# SOCUSBHSPHY.net
KiCad netlist of a schematic drawn in Altium Designer
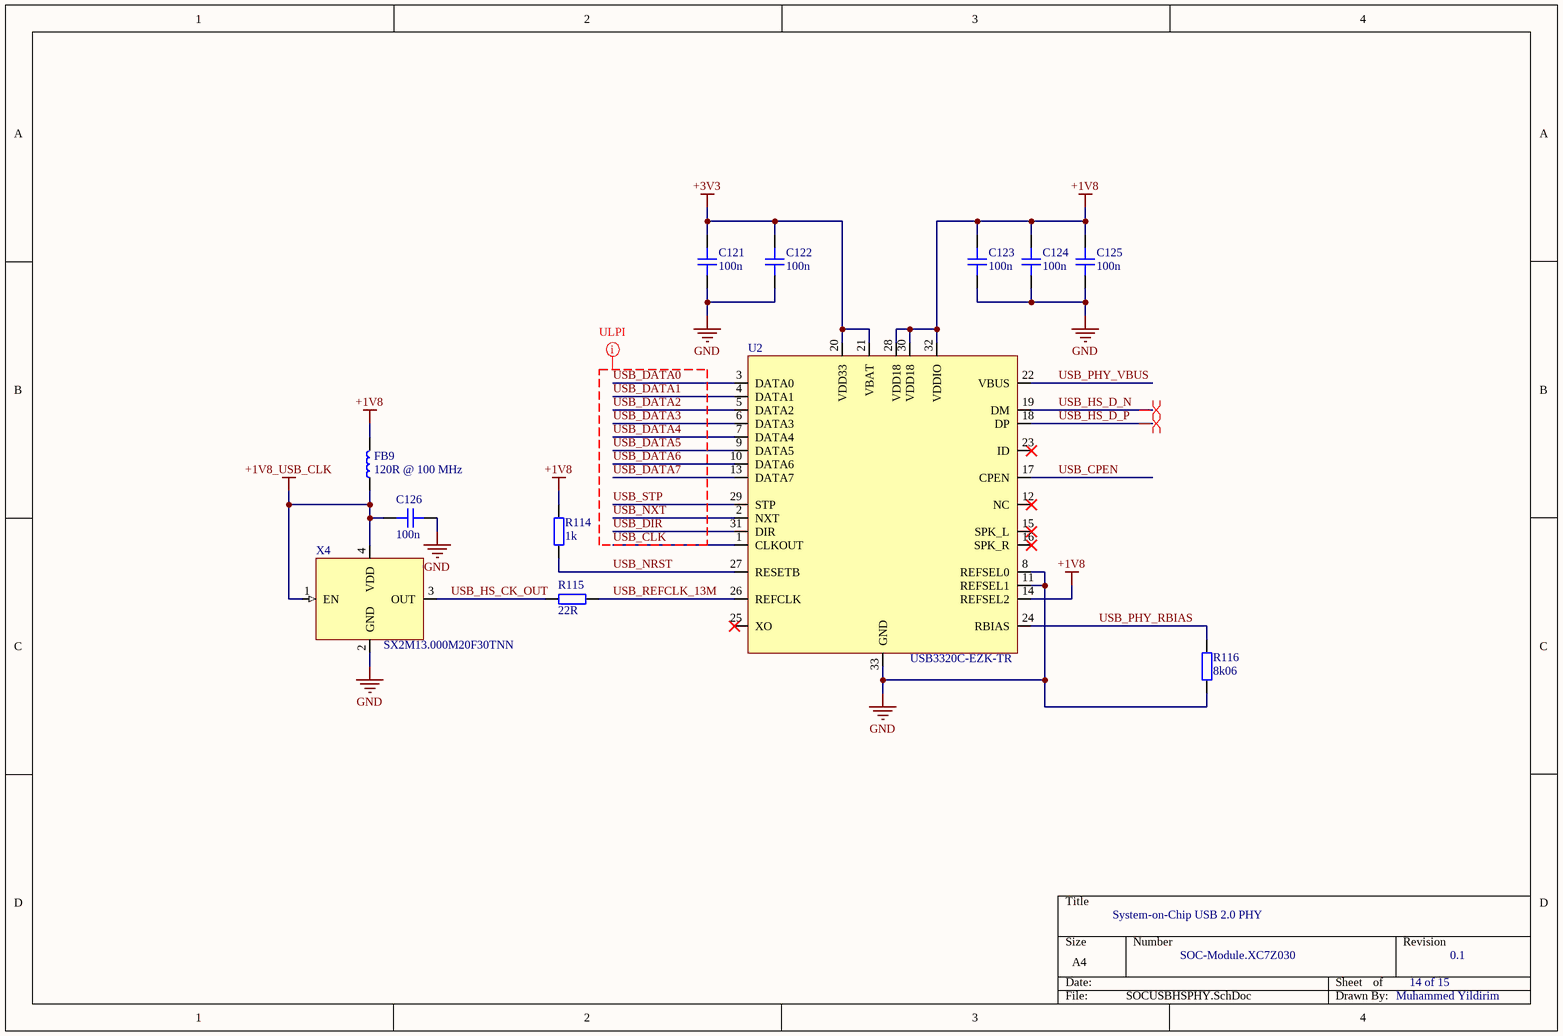
[diagram p0: SOCUSBHSPHY.SchDoc]

(export (version "E")
  (design (tool "Eeschema 10.0.6"))
  (components
    (comp (ref "C121")
      (value "100n")
      (footprint "CAP_0201")
      (description "Capacitor SMD 0201")
      (libsource (lib "Schematic-Lib-PhilsLab") (part "CAP_0201"))
    )
    (comp (ref "C122")
      (value "100n")
      (footprint "CAP_0201")
      (description "Capacitor SMD 0201")
      (libsource (lib "Schematic-Lib-PhilsLab") (part "CAP_0201"))
    )
    (comp (ref "C123")
      (value "100n")
      (footprint "CAP_0201")
      (description "Capacitor SMD 0201")
      (libsource (lib "Schematic-Lib-PhilsLab") (part "CAP_0201"))
    )
    (comp (ref "C124")
      (value "100n")
      (footprint "CAP_0201")
      (description "Capacitor SMD 0201")
      (libsource (lib "Schematic-Lib-PhilsLab") (part "CAP_0201"))
    )
    (comp (ref "C125")
      (value "100n")
      (footprint "CAP_0201")
      (description "Capacitor SMD 0201")
      (libsource (lib "Schematic-Lib-PhilsLab") (part "CAP_0201"))
    )
    (comp (ref "C126")
      (value "100n")
      (footprint "CAP_0201")
      (description "Capacitor SMD 0201")
      (libsource (lib "Schematic-Lib-PhilsLab") (part "CAP_0201"))
    )
    (comp (ref "FB9")
      (value "120R @ 100 MHz")
      (footprint "Footprint-Lib-PhilsLab:IND_0201")
      (description "Inductor SMD 0201")
      (fields
        (field (name "MANUFACTURER_PART_NUMBER") "LQP03HQ56NH02D")
        (field (name "MOUSER PART NUMBER") "81-LQP03HQ56NH02D")
      )
      (libsource (lib "Schematic-Lib-PhilsLab") (part "IND_0201"))
    )
    (comp (ref "R114")
      (value "1k")
      (footprint "RES_0201")
      (description "Resistor SMD 0201")
      (libsource (lib "Schematic-Lib-PhilsLab") (part "RES_0201"))
    )
    (comp (ref "R115")
      (value "22R")
      (footprint "RES_0201")
      (description "Resistor SMD 0201")
      (libsource (lib "Schematic-Lib-PhilsLab") (part "RES_0201"))
    )
    (comp (ref "R116")
      (value "8k06")
      (footprint "RES_0201")
      (description "Resistor SMD 0201")
      (libsource (lib "Schematic-Lib-PhilsLab") (part "RES_0201"))
    )
    (comp (ref "U2")
      (value "USB3320C-EZK-TR")
      (footprint "QFN-32-5x5x0.85mm")
      (description "Hi-Speed USB 2.0 ULPI Transceiver")
      (fields (field (name "MANUFACTURER") "Microchip"))
      (libsource (lib "Schematic-Lib-PhilsLab") (part "USB3320C-EZK-TR"))
    )
    (comp (ref "X4")
      (value "SX2M13.000M20F30TNN")
      (footprint "XTAL_2520")
      (fields
        (field (name "MANUFACTURER") "ECS")
        (field (name "MANUFACTURER PART NUMBER") "ECS-2520MV-130-BN-TR")
      )
      (libsource (lib "Schematic-Lib-PhilsLab") (part "ECS-2520MV-130-BN-TR"))
    )
  )
  (nets
    (net (code "1") (name "+1V8") (class "Default")
      (node (ref "C123") (pin "2") (pinfunction "2_2") (pintype "passive"))
      (node (ref "C124") (pin "2") (pinfunction "2_2") (pintype "passive"))
      (node (ref "C125") (pin "2") (pinfunction "2_2") (pintype "passive"))
      (node (ref "FB9") (pin "2") (pinfunction "2_2") (pintype "passive"))
      (node (ref "R114") (pin "1") (pinfunction "1_1") (pintype "passive"))
      (node (ref "U2") (pin "14") (pinfunction "REFSEL2_14") (pintype "passive"))
      (node (ref "U2") (pin "28") (pinfunction "VDD18_28") (pintype "passive"))
      (node (ref "U2") (pin "30") (pinfunction "VDD18_30") (pintype "passive"))
      (node (ref "U2") (pin "32") (pinfunction "VDDIO_32") (pintype "passive"))
    )
    (net (code "2") (name "+1V8_USB_CLK") (class "Default")
      (node (ref "C126") (pin "2") (pinfunction "2_2") (pintype "passive"))
      (node (ref "FB9") (pin "1") (pinfunction "1_1") (pintype "passive"))
      (node (ref "X4") (pin "1") (pinfunction "EN_1") (pintype "input"))
      (node (ref "X4") (pin "4") (pinfunction "VDD_4") (pintype "power_in"))
    )
    (net (code "3") (name "+3V3") (class "Default")
      (node (ref "C121") (pin "2") (pinfunction "2_2") (pintype "passive"))
      (node (ref "C122") (pin "2") (pinfunction "2_2") (pintype "passive"))
      (node (ref "U2") (pin "20") (pinfunction "VDD33_20") (pintype "passive"))
      (node (ref "U2") (pin "21") (pinfunction "VBAT_21") (pintype "passive"))
    )
    (net (code "4") (name "/USB_CLK") (class "Default")
      (node (ref "U2") (pin "1") (pinfunction "CLKOUT_1") (pintype "passive"))
    )
    (net (code "5") (name "/USB_CPEN") (class "Default")
      (node (ref "U2") (pin "17") (pinfunction "CPEN_17") (pintype "passive"))
    )
    (net (code "6") (name "/USB_DATA0") (class "Default")
      (node (ref "U2") (pin "3") (pinfunction "DATA0_3") (pintype "passive"))
    )
    (net (code "7") (name "/USB_DATA1") (class "Default")
      (node (ref "U2") (pin "4") (pinfunction "DATA1_4") (pintype "passive"))
    )
    (net (code "8") (name "/USB_DATA2") (class "Default")
      (node (ref "U2") (pin "5") (pinfunction "DATA2_5") (pintype "passive"))
    )
    (net (code "9") (name "/USB_DATA3") (class "Default")
      (node (ref "U2") (pin "6") (pinfunction "DATA3_6") (pintype "passive"))
    )
    (net (code "10") (name "/USB_DATA4") (class "Default")
      (node (ref "U2") (pin "7") (pinfunction "DATA4_7") (pintype "passive"))
    )
    (net (code "11") (name "/USB_DATA5") (class "Default")
      (node (ref "U2") (pin "9") (pinfunction "DATA5_9") (pintype "passive"))
    )
    (net (code "12") (name "/USB_DATA6") (class "Default")
      (node (ref "U2") (pin "10") (pinfunction "DATA6_10") (pintype "passive"))
    )
    (net (code "13") (name "/USB_DATA7") (class "Default")
      (node (ref "U2") (pin "13") (pinfunction "DATA7_13") (pintype "passive"))
    )
    (net (code "14") (name "/USB_DIR") (class "Default")
      (node (ref "U2") (pin "31") (pinfunction "DIR_31") (pintype "passive"))
    )
    (net (code "15") (name "/USB_HS_CK_OUT") (class "Default")
      (node (ref "R115") (pin "1") (pinfunction "1_1") (pintype "passive"))
      (node (ref "X4") (pin "3") (pinfunction "OUT_3") (pintype "passive"))
    )
    (net (code "16") (name "/USB_HS_D_N") (class "Default")
      (node (ref "U2") (pin "19") (pinfunction "DM_19") (pintype "passive"))
    )
    (net (code "17") (name "/USB_HS_D_P") (class "Default")
      (node (ref "U2") (pin "18") (pinfunction "DP_18") (pintype "passive"))
    )
    (net (code "18") (name "/USB_NRST") (class "Default")
      (node (ref "R114") (pin "2") (pinfunction "2_2") (pintype "passive"))
      (node (ref "U2") (pin "27") (pinfunction "RESETB_27") (pintype "passive"))
    )
    (net (code "19") (name "/USB_NXT") (class "Default")
      (node (ref "U2") (pin "2") (pinfunction "NXT_2") (pintype "passive"))
    )
    (net (code "20") (name "/USB_PHY_RBIAS") (class "Default")
      (node (ref "R116") (pin "2") (pinfunction "2_2") (pintype "passive"))
      (node (ref "U2") (pin "24") (pinfunction "RBIAS_24") (pintype "passive"))
    )
    (net (code "21") (name "/USB_PHY_VBUS") (class "Default")
      (node (ref "U2") (pin "22") (pinfunction "VBUS_22") (pintype "passive"))
    )
    (net (code "22") (name "/USB_REFCLK_13M") (class "Default")
      (node (ref "R115") (pin "2") (pinfunction "2_2") (pintype "passive"))
      (node (ref "U2") (pin "26") (pinfunction "REFCLK_26") (pintype "passive"))
    )
    (net (code "23") (name "/USB_STP") (class "Default")
      (node (ref "U2") (pin "29") (pinfunction "STP_29") (pintype "passive"))
    )
    (net (code "24") (name "GND") (class "Default")
      (node (ref "C121") (pin "1") (pinfunction "1_1") (pintype "passive"))
      (node (ref "C122") (pin "1") (pinfunction "1_1") (pintype "passive"))
      (node (ref "C123") (pin "1") (pinfunction "1_1") (pintype "passive"))
      (node (ref "C124") (pin "1") (pinfunction "1_1") (pintype "passive"))
      (node (ref "C125") (pin "1") (pinfunction "1_1") (pintype "passive"))
      (node (ref "C126") (pin "1") (pinfunction "1_1") (pintype "passive"))
      (node (ref "R116") (pin "1") (pinfunction "1_1") (pintype "passive"))
      (node (ref "U2") (pin "11") (pinfunction "REFSEL1_11") (pintype "passive"))
      (node (ref "U2") (pin "33") (pinfunction "GND_33") (pintype "passive"))
      (node (ref "U2") (pin "8") (pinfunction "REFSEL0_8") (pintype "passive"))
      (node (ref "X4") (pin "2") (pinfunction "GND_2") (pintype "power_in"))
    )
    (net (code "25") (name "unconnected-(U2-ID-Pad23)") (class "Default")
      (node (ref "U2") (pin "23") (pinfunction "ID_23") (pintype "passive+no_connect"))
    )
    (net (code "26") (name "unconnected-(U2-NC-Pad12)") (class "Default")
      (node (ref "U2") (pin "12") (pinfunction "NC_12") (pintype "passive+no_connect"))
    )
    (net (code "27") (name "unconnected-(U2-SPK_L-Pad15)") (class "Default")
      (node (ref "U2") (pin "15") (pinfunction "SPK_L_15") (pintype "passive+no_connect"))
    )
    (net (code "28") (name "unconnected-(U2-SPK_R-Pad16)") (class "Default")
      (node (ref "U2") (pin "16") (pinfunction "SPK_R_16") (pintype "passive+no_connect"))
    )
    (net (code "29") (name "unconnected-(U2-XO-Pad25)") (class "Default")
      (node (ref "U2") (pin "25") (pinfunction "XO_25") (pintype "passive+no_connect"))
    )
  )
)
